# 1.net
KiCad netlist of a schematic drawn in Altium Designer
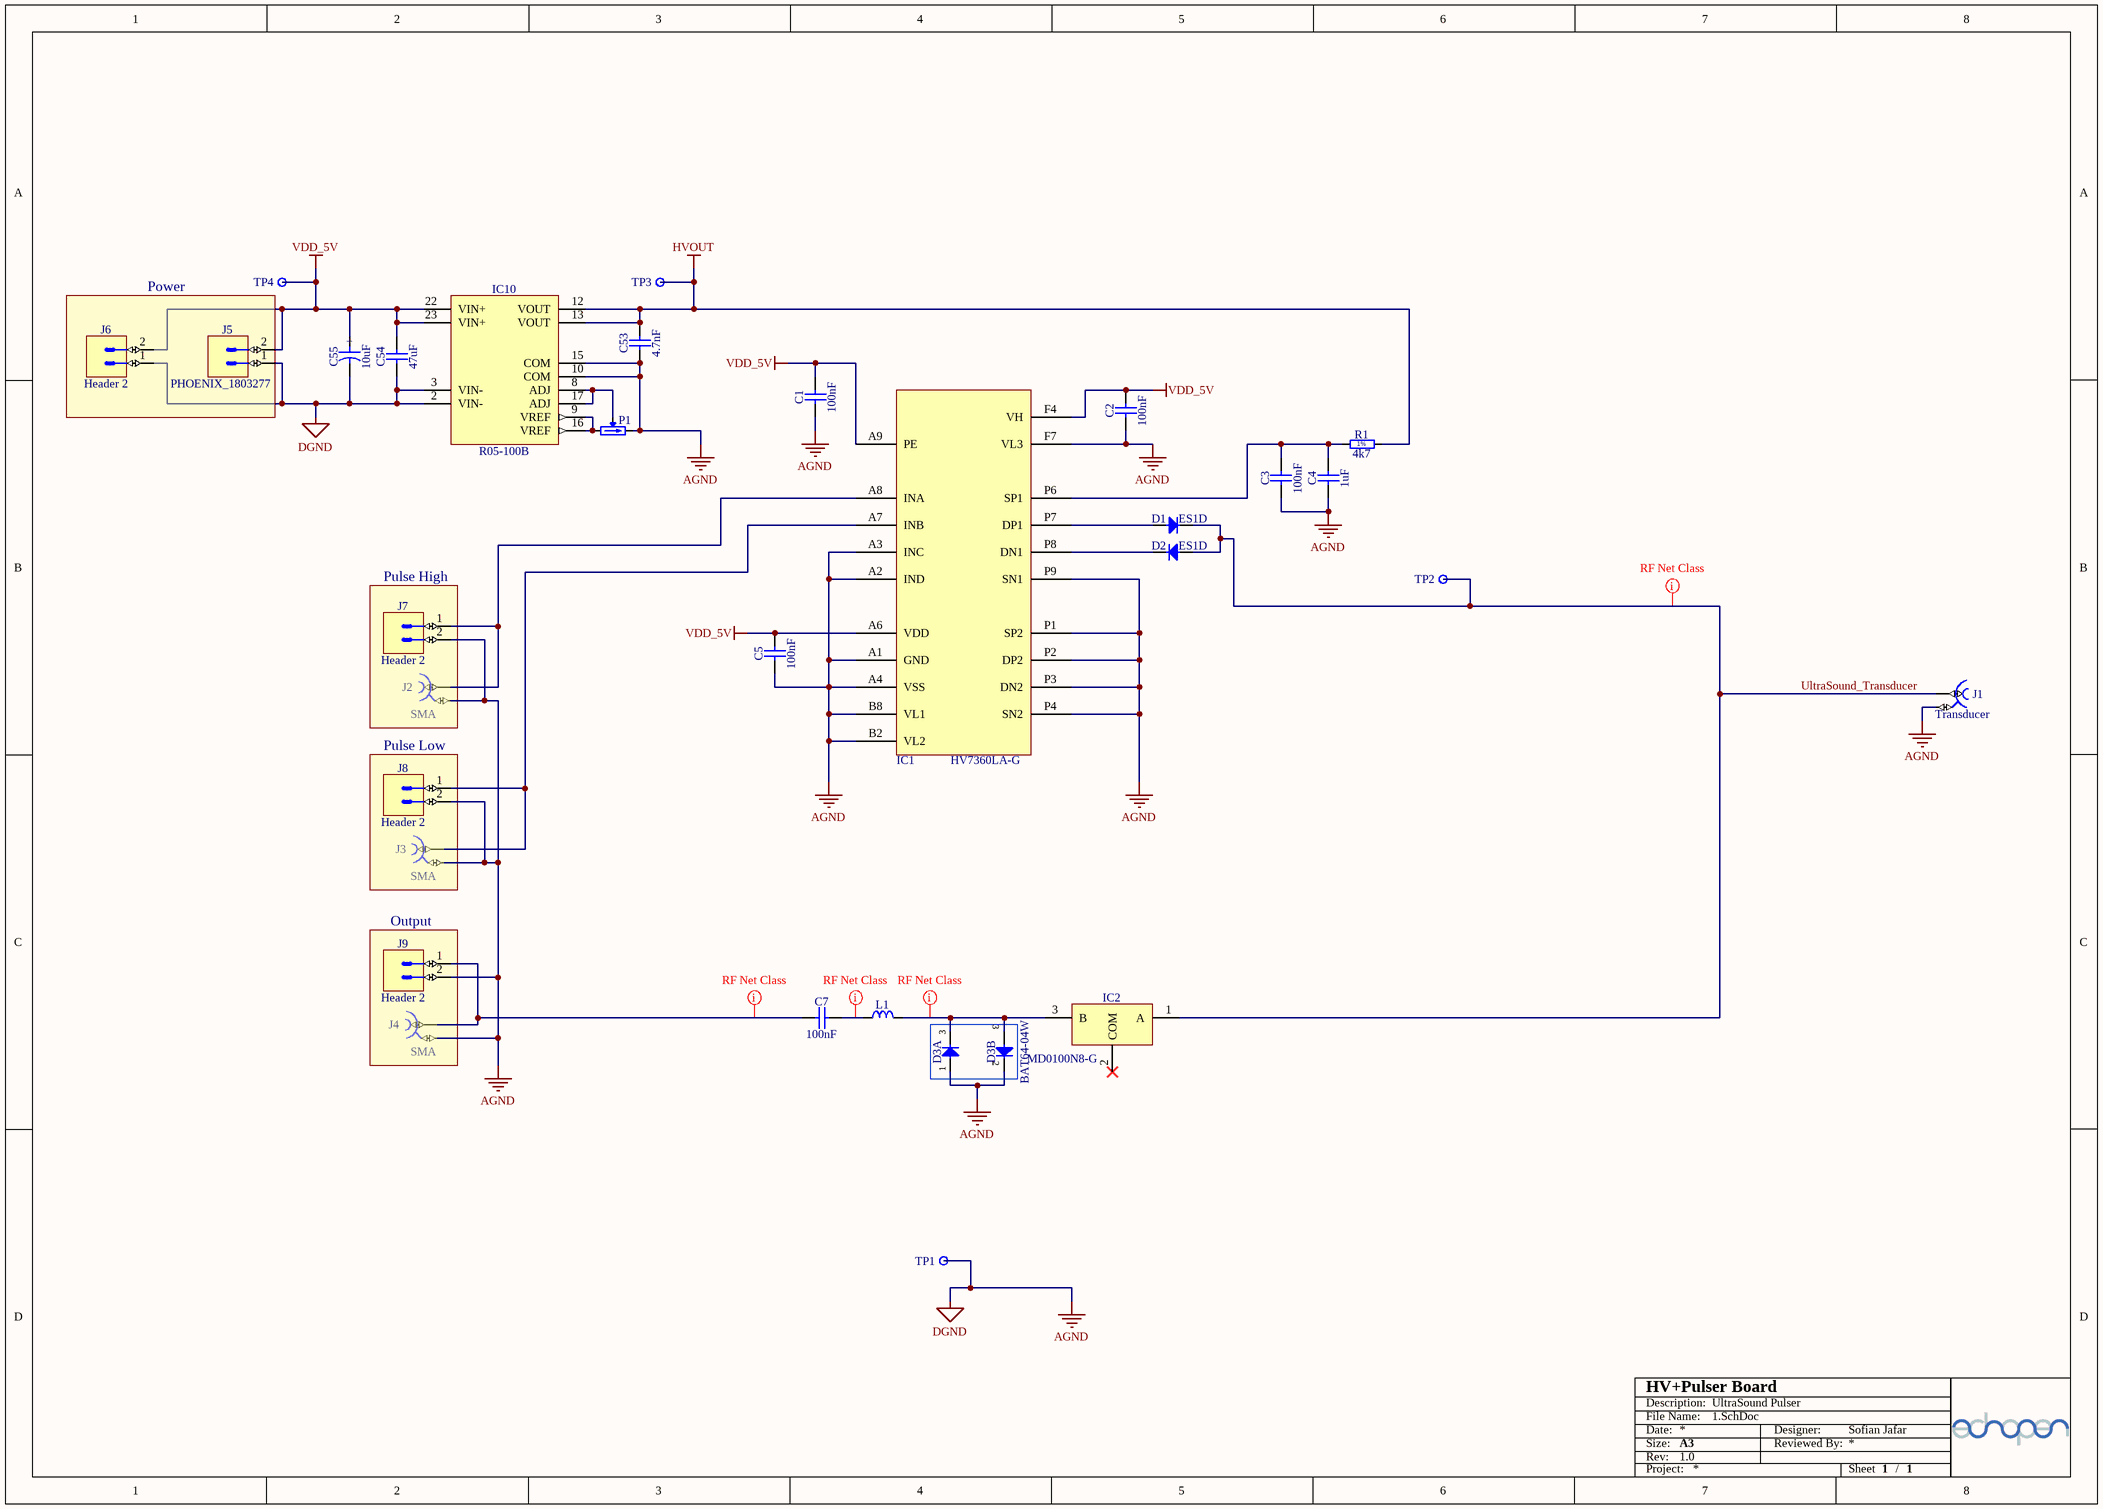
[diagram p0: 1.SchDoc]

(export (version "E")
  (design (tool "Eeschema 10.0.6"))
  (components
    (comp (ref "C1")
      (value "100nF")
      (footprint "CAPC1608X87N")
      (description "Non-polarised capacitor")
      (fields
        (field (name "PART NUMBER") "CC0603_100NF_50V_10%_X7R")
        (field (name "VOLTAGE") "50V")
        (field (name "AUTHOR") "CERN DEM JLC")
      )
      (libsource (lib "Sof-Capacitors") (part "Capacitor - non polarized"))
    )
    (comp (ref "C2")
      (value "100nF")
      (footprint "CAPC1608X87N")
      (description "Non-polarised capacitor")
      (fields
        (field (name "PART NUMBER") "CC0603_100NF_50V_10%_X7R")
        (field (name "VOLTAGE") "50V")
        (field (name "AUTHOR") "CERN DEM JLC")
      )
      (libsource (lib "Sof-Capacitors") (part "Capacitor - non polarized"))
    )
    (comp (ref "C3")
      (value "100nF")
      (footprint "CAPC1608X87N")
      (description "Non-polarised capacitor")
      (fields
        (field (name "PART NUMBER") "CC0603_100NF_50V_10%_X7R")
        (field (name "VOLTAGE") "50V")
        (field (name "AUTHOR") "CERN DEM JLC")
      )
      (libsource (lib "Sof-Capacitors") (part "Capacitor - non polarized"))
    )
    (comp (ref "C4")
      (value "1uF")
      (footprint "CAPC5650X165N")
      (description "Non-polarised capacitor")
      (fields
        (field (name "PART NUMBER") "CC2220_1UF_200V_10%_X7R")
        (field (name "VOLTAGE") "200V")
        (field (name "AUTHOR") "CERN DEM JLC")
      )
      (libsource (lib "Sof-Capacitors") (part "Capacitor - non polarized"))
    )
    (comp (ref "C5")
      (value "100nF")
      (footprint "CAPC1608X87N")
      (description "Non-polarised capacitor")
      (fields
        (field (name "PART NUMBER") "CC0603_100NF_50V_10%_X7R")
        (field (name "VOLTAGE") "50V")
        (field (name "AUTHOR") "CERN DEM JLC")
      )
      (libsource (lib "Sof-Capacitors") (part "Capacitor - non polarized"))
    )
    (comp (ref "C7")
      (value "100nF")
      (footprint "CAPC1608X87N")
      (description "Non-polarised capacitor")
      (fields
        (field (name "PART NUMBER") "CC0603_100NF_50V_10%_X7R")
        (field (name "VOLTAGE") "50V")
        (field (name "AUTHOR") "CERN DEM JLC")
      )
      (libsource (lib "Sof-Capacitors") (part "Capacitor - non polarized"))
    )
    (comp (ref "C53")
      (value "4.7nF")
      (footprint "CAPC2012X110N")
      (description "Non-polarised capacitor")
      (fields
        (field (name "PART NUMBER") "CC0805_4.7NF_250V_10%_X7R")
        (field (name "VOLTAGE") "250V")
        (field (name "AUTHOR") "S. Jafar")
      )
      (libsource (lib "Sof-Capacitors") (part "Capacitor - non polarized"))
    )
    (comp (ref "C54")
      (value "47uF")
      (footprint "CAPC3216X180N")
      (description "Non-polarised capacitor")
      (fields
        (field (name "PART NUMBER") "CC1206_47UF_25V_20%_X5R")
        (field (name "VOLTAGE") "25V")
        (field (name "AUTHOR") "CERN DEM JLC")
      )
      (libsource (lib "Sof-Capacitors") (part "Capacitor - non polarized"))
    )
    (comp (ref "C55")
      (value "10uF")
      (footprint "CAPMP3528X210N")
      (description "Polarised capacitor")
      (fields
        (field (name "PART NUMBER") "CTE3528-21_10UF_16V_10%_LESR0800")
        (field (name "VOLTAGE") "16V")
        (field (name "AUTHOR") "CERN DEM JLC")
      )
      (libsource (lib "Sof-Capacitors") (part "Capacitor - polarized"))
    )
    (comp (ref "D1")
      (value "ES1D")
      (footprint "DIOM5027X244N")
      (description "Diode")
      (fields
        (field (name "VOLTAGE") "200V")
        (field (name "POWER") "1A")
        (field (name "AUTHOR") "CERN DEM JLC")
      )
      (libsource (lib "Sof-ICs And Semiconductors") (part "Diode"))
    )
    (comp (ref "D2")
      (value "ES1D")
      (footprint "DIOM5027X244N")
      (description "Diode")
      (fields
        (field (name "VOLTAGE") "200V")
        (field (name "POWER") "1A")
        (field (name "AUTHOR") "CERN DEM JLC")
      )
      (libsource (lib "Sof-ICs And Semiconductors") (part "Diode"))
    )
    (comp (ref "D3")
      (value "BAT64-04W")
      (footprint "SOT65P210X100-3N")
      (description "Serial Diode")
      (fields
        (field (name "VOLTAGE") "40V")
        (field (name "POWER") "250mW")
        (field (name "AUTHOR") "CERN DEM JMW")
      )
      (libsource (lib "Sof-ICs And Semiconductors") (part "Diode x2 A1C3_A3C2"))
    )
    (comp (ref "IC1")
      (value "HV7360LA-G")
      (footprint "HV7360")
      (fields (field (name "MANUFACTURER") "Supertex inc.") (field (name "AUTHOR") "S. Jafar"))
      (libsource (lib "Sof-ICs And Semiconductors") (part "HV7360"))
    )
    (comp (ref "IC2")
      (value "MD0100N8-G")
      (footprint "SOT89")
      (description "3-Ultra-Sound HV Switch 1=A 2=COM 3=B")
      (fields (field (name "MANUFACTURER") "Supertex inc.") (field (name "AUTHOR") "S. Jafar"))
      (libsource (lib "Sof-ICs And Semiconductors") (part "MD0100"))
    )
    (comp (ref "IC10")
      (value "R05-100B")
      (footprint "PWS_RECOM_R05-100B")
      (description "Power Supply")
      (fields (field (name "MANUFACTURER") "RECOM POWER") (field (name "AUTHOR") "S. Jafar"))
      (libsource (lib "Sof-ICs And Semiconductors") (part "PWS_RECOM_R05-100B"))
    )
    (comp (ref "J1")
      (value "Transducer")
      (footprint "AMPHENOL_132357-11")
      (fields
        (field (name "PART NUMBER") "AMPHENOL_132357-11")
        (field (name "MANUFACTURER") "AMPHENOL")
        (field (name "MANUFACTURER PART NUMBER") "132357-11")
        (field (name "AUTHOR") "CERN DEM JLC")
      )
      (libsource (lib "") (part "Coax_1Female_1Shield_1"))
    )
    (comp (ref "J2")
      (value "SMA")
      (footprint "AMPHENOL_132357-11")
      (fields
        (field (name "PART NUMBER") "AMPHENOL_132357-11")
        (field (name "MANUFACTURER") "AMPHENOL")
        (field (name "MANUFACTURER PART NUMBER") "132357-11")
        (field (name "AUTHOR") "CERN DEM JLC")
      )
      (libsource (lib "Sof-Connectors") (part "Coax_1Female_1Shield"))
    )
    (comp (ref "J3")
      (value "SMA")
      (footprint "AMPHENOL_132357-11")
      (fields
        (field (name "PART NUMBER") "AMPHENOL_132357-11")
        (field (name "MANUFACTURER") "AMPHENOL")
        (field (name "MANUFACTURER PART NUMBER") "132357-11")
        (field (name "AUTHOR") "CERN DEM JLC")
      )
      (libsource (lib "Sof-Connectors") (part "Coax_1Female_1Shield"))
    )
    (comp (ref "J4")
      (value "SMA")
      (footprint "AMPHENOL_132357-11")
      (fields
        (field (name "PART NUMBER") "AMPHENOL_132357-11")
        (field (name "MANUFACTURER") "AMPHENOL")
        (field (name "MANUFACTURER PART NUMBER") "132357-11")
        (field (name "AUTHOR") "CERN DEM JLC")
      )
      (libsource (lib "Sof-Connectors") (part "Coax_1Female_1Shield"))
    )
    (comp (ref "J5")
      (value "PHOENIX_1803277")
      (footprint "PHOENIX_1803277")
      (description "Connector 2 Male")
      (fields
        (field (name "MANUFACTURER") "PHOENIX CONTACT")
        (field (name "MANUFACTURER PART NUMBER") "1803277 (MC 1,5/ 2-G-3,81)")
        (field (name "AUTHOR") "CERN DEM JLC")
      )
      (libsource (lib "") (part "Connector 2 Male_1"))
    )
    (comp (ref "J6")
      (value "Header 2")
      (footprint "HARWIN_M20-9990246")
      (description "Connector 2 Male")
      (fields
        (field (name "PART NUMBER") "HARWIN_M20-9990246_a")
        (field (name "MANUFACTURER") "HARWIN")
        (field (name "AUTHOR") "S. Jafar")
      )
      (libsource (lib "") (part "Connector 2 Male_1"))
    )
    (comp (ref "J7")
      (value "Header 2")
      (footprint "HARWIN_M20-9990246")
      (description "Connector 2 Male")
      (fields
        (field (name "PART NUMBER") "HARWIN_M20-9990246_a")
        (field (name "MANUFACTURER") "HARWIN")
        (field (name "AUTHOR") "S. Jafar")
      )
      (libsource (lib "Sof-Connectors") (part "Connector 2 Male"))
    )
    (comp (ref "J8")
      (value "Header 2")
      (footprint "HARWIN_M20-9990246")
      (description "Connector 2 Male")
      (fields
        (field (name "PART NUMBER") "HARWIN_M20-9990246_a")
        (field (name "MANUFACTURER") "HARWIN")
        (field (name "AUTHOR") "S. Jafar")
      )
      (libsource (lib "Sof-Connectors") (part "Connector 2 Male"))
    )
    (comp (ref "J9")
      (value "Header 2")
      (footprint "HARWIN_M20-9990246")
      (description "Connector 2 Male")
      (fields
        (field (name "PART NUMBER") "HARWIN_M20-9990246_a")
        (field (name "MANUFACTURER") "HARWIN")
        (field (name "AUTHOR") "S. Jafar")
      )
      (libsource (lib "Sof-Connectors") (part "Connector 2 Male"))
    )
    (comp (ref "L1")
      (value "75R@100MHz")
      (footprint "INDC2012X105N")
      (description "Inductor")
      (fields
        (field (name "PART NUMBER") "IND0805_MURATA_BLM21BB750SN1D")
        (field (name "POWER") "700mA")
        (field (name "AUTHOR") "S. Jafar")
      )
      (libsource (lib "Sof-Inductors & Transformers") (part "Inductor"))
    )
    (comp (ref "P1")
      (value "5k")
      (footprint "TRIM_BOURNS_3223W")
      (description "Trimming Potentiometer")
      (fields
        (field (name "PART NUMBER") "TRIM_11T_5K_BOURNS_3223W-1-502E")
        (field (name "POWER") "0.125W")
        (field (name "AUTHOR") "CERN DEM JLC")
      )
      (libsource (lib "Sof-Resistors") (part "Trimming Potentiometer"))
    )
    (comp (ref "R1")
      (value "4k7")
      (footprint "RESC3216X65N")
      (description "Resistor - 1%")
      (fields
        (field (name "PART NUMBER") "R1206_4K7_1%_0.25W_100PPM")
        (field (name "POWER") "0.25W")
        (field (name "AUTHOR") "CERN DEM JLC")
      )
      (libsource (lib "Sof-Resistors") (part "Resistor - 1%"))
    )
    (comp (ref "TP1")
      (value "Test Point")
      (footprint "NICOMATIC_C12000B")
      (fields
        (field (name "PART NUMBER") "NICOMATIC_C12000B")
        (field (name "MANUFACTURER") "NICOMATIC")
        (field (name "MANUFACTURER PART NUMBER") "C12000B")
        (field (name "AUTHOR") "CERN DEM JLC")
      )
      (libsource (lib "Sof-Connectors") (part "Test Point"))
    )
    (comp (ref "TP2")
      (value "Test Point")
      (footprint "NICOMATIC_C12000B")
      (fields
        (field (name "PART NUMBER") "NICOMATIC_C12000B")
        (field (name "MANUFACTURER") "NICOMATIC")
        (field (name "MANUFACTURER PART NUMBER") "C12000B")
        (field (name "AUTHOR") "CERN DEM JLC")
      )
      (libsource (lib "Sof-Connectors") (part "Test Point"))
    )
    (comp (ref "TP3")
      (value "Test Point")
      (footprint "NICOMATIC_C12000B")
      (fields
        (field (name "PART NUMBER") "NICOMATIC_C12000B")
        (field (name "MANUFACTURER") "NICOMATIC")
        (field (name "MANUFACTURER PART NUMBER") "C12000B")
        (field (name "AUTHOR") "CERN DEM JLC")
      )
      (libsource (lib "Sof-Connectors") (part "Test Point"))
    )
    (comp (ref "TP4")
      (value "Test Point")
      (footprint "NICOMATIC_C12000B")
      (fields
        (field (name "PART NUMBER") "NICOMATIC_C12000B")
        (field (name "MANUFACTURER") "NICOMATIC")
        (field (name "MANUFACTURER PART NUMBER") "C12000B")
        (field (name "AUTHOR") "CERN DEM JLC")
      )
      (libsource (lib "Sof-Connectors") (part "Test Point"))
    )
  )
  (nets
    (net (code "1") (name "/UltraSound_Transducer") (class "Default")
      (node (ref "D1") (pin "1") (pinfunction "C_1") (pintype "passive"))
      (node (ref "D2") (pin "2") (pinfunction "A_2") (pintype "passive"))
      (node (ref "IC2") (pin "1") (pinfunction "A_1") (pintype "passive"))
      (node (ref "J1") (pin "1") (pinfunction "1_1") (pintype "bidirectional"))
      (node (ref "TP2") (pin "1") (pinfunction "1_1") (pintype "bidirectional"))
    )
    (net (code "2") (name "AGND") (class "Default")
      (node (ref "C1") (pin "1") (pinfunction "1_1") (pintype "passive"))
      (node (ref "C2") (pin "1") (pinfunction "1_1") (pintype "passive"))
      (node (ref "C3") (pin "1") (pinfunction "1_1") (pintype "passive"))
      (node (ref "C4") (pin "1") (pinfunction "1_1") (pintype "passive"))
      (node (ref "C5") (pin "1") (pinfunction "1_1") (pintype "passive"))
      (node (ref "C53") (pin "1") (pinfunction "1_1") (pintype "passive"))
      (node (ref "C54") (pin "1") (pinfunction "1_1") (pintype "passive"))
      (node (ref "C55") (pin "2") (pinfunction "2_2") (pintype "passive"))
      (node (ref "D3") (pin "1") (pinfunction "A_1") (pintype "passive"))
      (node (ref "D3") (pin "2") (pinfunction "C_2") (pintype "passive"))
      (node (ref "IC1") (pin "A1") (pinfunction "GND_A1") (pintype "passive"))
      (node (ref "IC1") (pin "A2") (pinfunction "IND_A2") (pintype "passive"))
      (node (ref "IC1") (pin "A3") (pinfunction "INC_A3") (pintype "passive"))
      (node (ref "IC1") (pin "A4") (pinfunction "VSS_A4") (pintype "passive"))
      (node (ref "IC1") (pin "B2") (pinfunction "VL2_B2") (pintype "passive"))
      (node (ref "IC1") (pin "B8") (pinfunction "VL1_B8") (pintype "passive"))
      (node (ref "IC1") (pin "F7") (pinfunction "VL3_F7") (pintype "passive"))
      (node (ref "IC1") (pin "P1") (pinfunction "SP2_P1") (pintype "passive"))
      (node (ref "IC1") (pin "P2") (pinfunction "DP2_P2") (pintype "passive"))
      (node (ref "IC1") (pin "P3") (pinfunction "DN2_P3") (pintype "passive"))
      (node (ref "IC1") (pin "P4") (pinfunction "SN2_P4") (pintype "passive"))
      (node (ref "IC1") (pin "P9") (pinfunction "SN1_P9") (pintype "passive"))
      (node (ref "IC10") (pin "10") (pinfunction "COM_10") (pintype "power_in"))
      (node (ref "IC10") (pin "15") (pinfunction "COM_15") (pintype "power_in"))
      (node (ref "IC10") (pin "2") (pinfunction "VIN-_2") (pintype "passive"))
      (node (ref "IC10") (pin "3") (pinfunction "VIN-_3") (pintype "passive"))
      (node (ref "J1") (pin "2") (pinfunction "2_2") (pintype "bidirectional"))
      (node (ref "J2") (pin "2") (pinfunction "2_2") (pintype "bidirectional"))
      (node (ref "J3") (pin "2") (pinfunction "2_2") (pintype "bidirectional"))
      (node (ref "J4") (pin "2") (pinfunction "2_2") (pintype "bidirectional"))
      (node (ref "J5") (pin "1") (pinfunction "1_1") (pintype "bidirectional"))
      (node (ref "J6") (pin "1") (pinfunction "1_1") (pintype "bidirectional"))
      (node (ref "J7") (pin "2") (pinfunction "2_2") (pintype "bidirectional"))
      (node (ref "J8") (pin "2") (pinfunction "2_2") (pintype "bidirectional"))
      (node (ref "J9") (pin "2") (pinfunction "2_2") (pintype "bidirectional"))
      (node (ref "P1") (pin "3") (pinfunction "CW_3") (pintype "passive"))
      (node (ref "TP1") (pin "1") (pinfunction "1_1") (pintype "bidirectional"))
    )
    (net (code "3") (name "HVOUT") (class "Default")
      (node (ref "C53") (pin "2") (pinfunction "2_2") (pintype "passive"))
      (node (ref "IC10") (pin "12") (pinfunction "VOUT_12") (pintype "power_in"))
      (node (ref "IC10") (pin "13") (pinfunction "VOUT_13") (pintype "power_in"))
      (node (ref "R1") (pin "2") (pinfunction "2_2") (pintype "passive"))
      (node (ref "TP3") (pin "1") (pinfunction "1_1") (pintype "bidirectional"))
    )
    (net (code "4") (name "Net-(C7-Pad1)") (class "Default")
      (node (ref "C7") (pin "1") (pinfunction "1_1") (pintype "passive"))
      (node (ref "L1") (pin "1") (pinfunction "1_1") (pintype "passive"))
    )
    (net (code "5") (name "Net-(C7-Pad2)") (class "Default")
      (node (ref "C7") (pin "2") (pinfunction "2_2") (pintype "passive"))
      (node (ref "J4") (pin "1") (pinfunction "1_1") (pintype "bidirectional"))
      (node (ref "J9") (pin "1") (pinfunction "1_1") (pintype "bidirectional"))
    )
    (net (code "6") (name "Net-(D1-A)") (class "Default")
      (node (ref "D1") (pin "2") (pinfunction "A_2") (pintype "passive"))
      (node (ref "IC1") (pin "P7") (pinfunction "DP1_P7") (pintype "passive"))
    )
    (net (code "7") (name "Net-(D2-C)") (class "Default")
      (node (ref "D2") (pin "1") (pinfunction "C_1") (pintype "passive"))
      (node (ref "IC1") (pin "P8") (pinfunction "DN1_P8") (pintype "passive"))
    )
    (net (code "8") (name "Net-(D3A-COMAC)") (class "Default")
      (node (ref "D3") (pin "3") (pinfunction "COMAC_3") (pintype "passive"))
      (node (ref "IC2") (pin "3") (pinfunction "B_3") (pintype "passive"))
      (node (ref "L1") (pin "2") (pinfunction "2_2") (pintype "passive"))
    )
    (net (code "9") (name "Net-(IC1-INA)") (class "Default")
      (node (ref "IC1") (pin "A8") (pinfunction "INA_A8") (pintype "passive"))
      (node (ref "J2") (pin "1") (pinfunction "1_1") (pintype "bidirectional"))
      (node (ref "J7") (pin "1") (pinfunction "1_1") (pintype "bidirectional"))
    )
    (net (code "10") (name "Net-(IC1-INB)") (class "Default")
      (node (ref "IC1") (pin "A7") (pinfunction "INB_A7") (pintype "passive"))
      (node (ref "J3") (pin "1") (pinfunction "1_1") (pintype "bidirectional"))
      (node (ref "J8") (pin "1") (pinfunction "1_1") (pintype "bidirectional"))
    )
    (net (code "11") (name "Net-(IC1-SP1)") (class "Default")
      (node (ref "C3") (pin "2") (pinfunction "2_2") (pintype "passive"))
      (node (ref "C4") (pin "2") (pinfunction "2_2") (pintype "passive"))
      (node (ref "IC1") (pin "P6") (pinfunction "SP1_P6") (pintype "passive"))
      (node (ref "R1") (pin "1") (pinfunction "1_1") (pintype "passive"))
    )
    (net (code "12") (name "Net-(P1-CCW)") (class "Default")
      (node (ref "IC10") (pin "16") (pinfunction "VREF_16") (pintype "output"))
      (node (ref "IC10") (pin "9") (pinfunction "VREF_9") (pintype "output"))
      (node (ref "P1") (pin "1") (pinfunction "CCW_1") (pintype "passive"))
    )
    (net (code "13") (name "Net-(P1-W)") (class "Default")
      (node (ref "IC10") (pin "17") (pinfunction "ADJ_17") (pintype "passive"))
      (node (ref "IC10") (pin "8") (pinfunction "ADJ_8") (pintype "passive"))
      (node (ref "P1") (pin "2") (pinfunction "W_2") (pintype "passive"))
    )
    (net (code "14") (name "VDD_5V") (class "Default")
      (node (ref "C1") (pin "2") (pinfunction "2_2") (pintype "passive"))
      (node (ref "C2") (pin "2") (pinfunction "2_2") (pintype "passive"))
      (node (ref "C5") (pin "2") (pinfunction "2_2") (pintype "passive"))
      (node (ref "C54") (pin "2") (pinfunction "2_2") (pintype "passive"))
      (node (ref "C55") (pin "1") (pinfunction "1_1") (pintype "passive"))
      (node (ref "IC1") (pin "A6") (pinfunction "VDD_A6") (pintype "passive"))
      (node (ref "IC1") (pin "A9") (pinfunction "PE_A9") (pintype "passive"))
      (node (ref "IC1") (pin "F4") (pinfunction "VH_F4") (pintype "passive"))
      (node (ref "IC10") (pin "22") (pinfunction "VIN+_22") (pintype "power_in"))
      (node (ref "IC10") (pin "23") (pinfunction "VIN+_23") (pintype "power_in"))
      (node (ref "J5") (pin "2") (pinfunction "2_2") (pintype "bidirectional"))
      (node (ref "J6") (pin "2") (pinfunction "2_2") (pintype "bidirectional"))
      (node (ref "TP4") (pin "1") (pinfunction "1_1") (pintype "bidirectional"))
    )
    (net (code "15") (name "unconnected-(IC2-COM-Pad2)") (class "Default")
      (node (ref "IC2") (pin "2") (pinfunction "COM_2") (pintype "passive+no_connect"))
    )
  )
)
